# Voltage_Current_Sense.net
KiCad netlist of a schematic drawn in Altium Designer
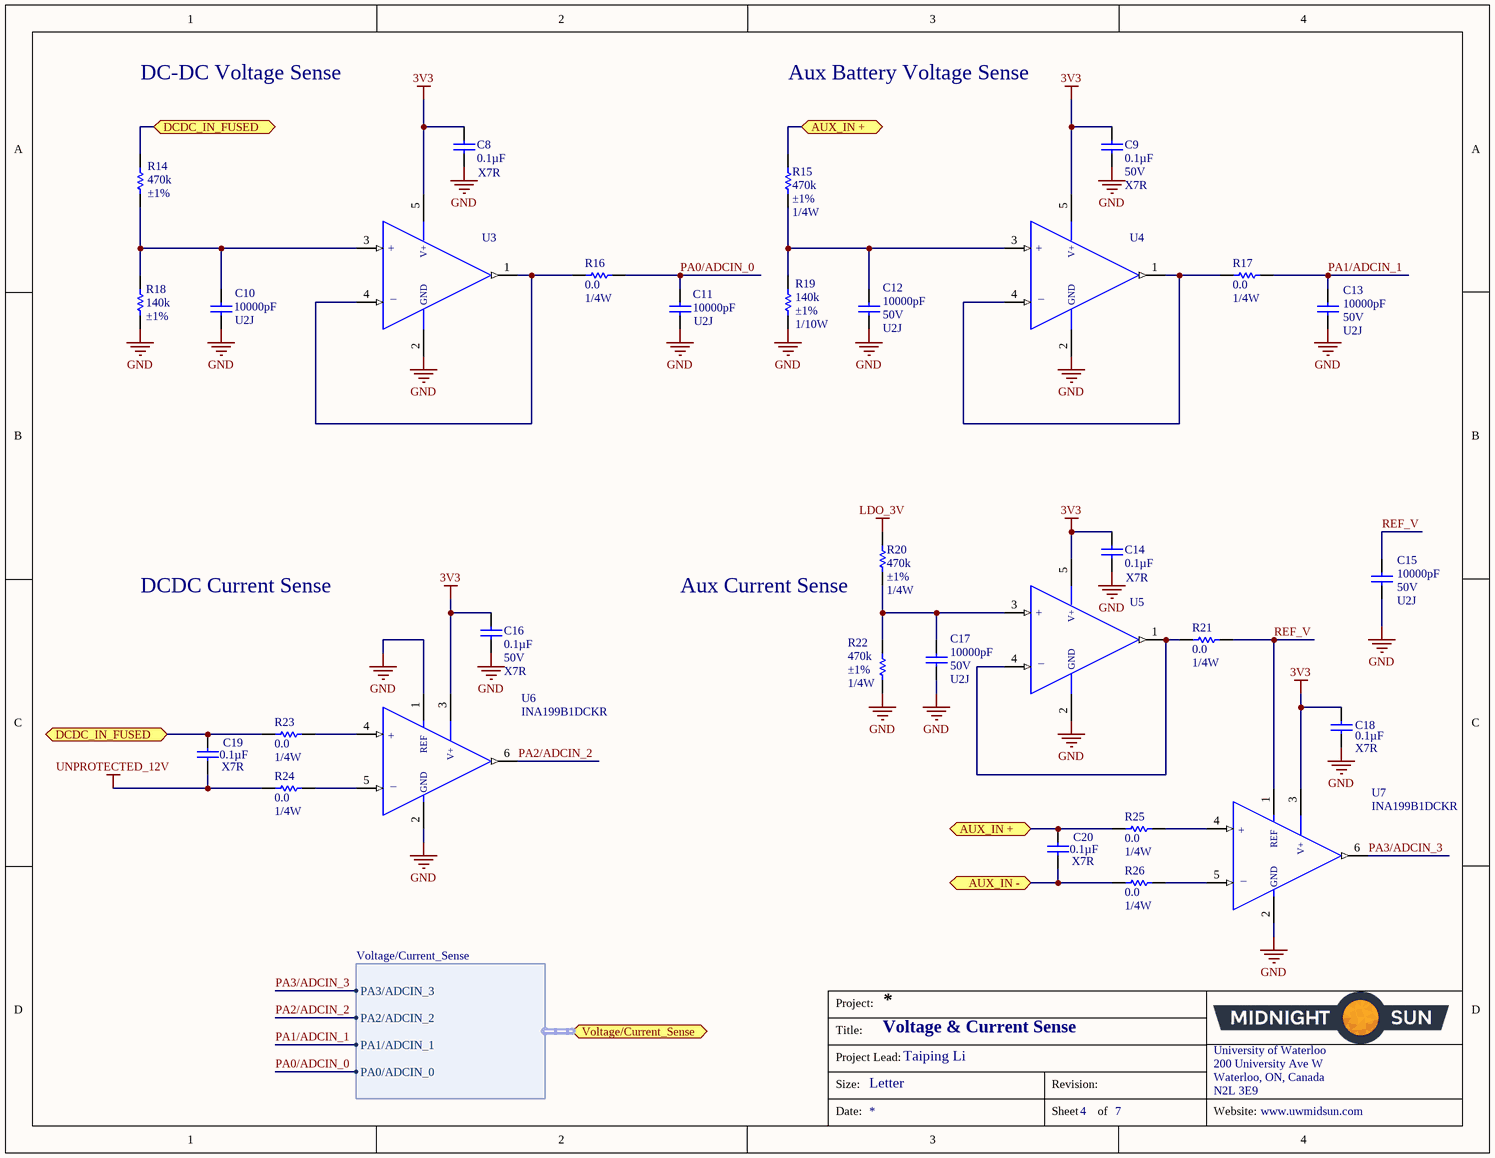
[diagram p0: Voltage&Current_Sense.SchDoc]

(export (version "E")
  (design (tool "Eeschema 10.0.6"))
  (components
    (comp (ref "C8")
      (value "CAP CER 0.1UF 50V 10% X7R 0603")
      (footprint "CAP, 0603")
      (description "0.10µF ±10% 50V Ceramic Capacitor X7R 0603 (1608 Metric)")
      (fields
        (field (name "TOLERANCE") "±10%")
        (field (name "CAPACITANCE") "0.1µF")
        (field (name "TEMPERATURE COEFFICIENT") "X7R")
      )
      (libsource (lib "Schematic Diagrams") (part "CAP CER 0.1UF 50V 10% X7R 0603"))
    )
    (comp (ref "C9")
      (value "CAP CER 0.1UF 50V 10% X7R 0603")
      (footprint "CAP, 0603")
      (description "0.10µF ±10% 50V Ceramic Capacitor X7R 0603 (1608 Metric)")
      (fields
        (field (name "TOLERANCE") "±10%")
        (field (name "CAPACITANCE") "0.1µF")
        (field (name "VOLTAGE") "50V")
        (field (name "TEMPERATURE COEFFICIENT") "X7R")
      )
      (libsource (lib "Schematic Diagrams") (part "CAP CER 0.1UF 50V 10% X7R 0603"))
    )
    (comp (ref "C10")
      (value "CAP CER 10nF 50V 5% X7R 0603")
      (footprint "CAP, 0603")
      (description "10000pF ±5% 50V Ceramic Capacitor U2J 0603 (1608 Metric)")
      (fields
        (field (name "TOLERANCE") "±5%")
        (field (name "CAPACITANCE") "10000pF")
        (field (name "TEMPERATURE COEFFICIENT") "U2J")
        (field (name "VOLTAGE") "50V")
      )
      (libsource (lib "Schematic Diagrams") (part "CAP CER 10nF 50V 5% X7R 0603"))
    )
    (comp (ref "C11")
      (value "CAP CER 10nF 50V 5% X7R 0603")
      (footprint "CAP, 0603")
      (description "10000pF ±5% 50V Ceramic Capacitor U2J 0603 (1608 Metric)")
      (fields
        (field (name "TOLERANCE") "±5%")
        (field (name "CAPACITANCE") "10000pF")
        (field (name "TEMPERATURE COEFFICIENT") "U2J")
        (field (name "VOLTAGE") "50V")
      )
      (libsource (lib "Schematic Diagrams") (part "CAP CER 10nF 50V 5% X7R 0603"))
    )
    (comp (ref "C12")
      (value "CAP CER 10nF 50V 5% X7R 0603")
      (footprint "CAP, 0603")
      (description "10000pF ±5% 50V Ceramic Capacitor U2J 0603 (1608 Metric)")
      (fields
        (field (name "TOLERANCE") "±5%")
        (field (name "CAPACITANCE") "10000pF")
        (field (name "VOLTAGE") "50V")
        (field (name "TEMPERATURE COEFFICIENT") "U2J")
      )
      (libsource (lib "Schematic Diagrams") (part "CAP CER 10nF 50V 5% X7R 0603"))
    )
    (comp (ref "C13")
      (value "CAP CER 10nF 50V 5% X7R 0603")
      (footprint "CAP, 0603")
      (description "10000pF ±5% 50V Ceramic Capacitor U2J 0603 (1608 Metric)")
      (fields
        (field (name "TOLERANCE") "±5%")
        (field (name "CAPACITANCE") "10000pF")
        (field (name "VOLTAGE") "50V")
        (field (name "TEMPERATURE COEFFICIENT") "U2J")
      )
      (libsource (lib "Schematic Diagrams") (part "CAP CER 10nF 50V 5% X7R 0603"))
    )
    (comp (ref "C14")
      (value "CAP CER 0.1UF 50V 10% X7R 0603")
      (footprint "CAP, 0603")
      (description "0.10µF ±10% 50V Ceramic Capacitor X7R 0603 (1608 Metric)")
      (fields
        (field (name "TOLERANCE") "±10%")
        (field (name "CAPACITANCE") "0.1µF")
        (field (name "TEMPERATURE COEFFICIENT") "X7R")
      )
      (libsource (lib "Schematic Diagrams") (part "CAP CER 0.1UF 50V 10% X7R 0603"))
    )
    (comp (ref "C15")
      (value "CAP CER 10nF 50V 5% X7R 0603")
      (footprint "CAP, 0603")
      (description "10000pF ±5% 50V Ceramic Capacitor U2J 0603 (1608 Metric)")
      (fields
        (field (name "TOLERANCE") "±5%")
        (field (name "CAPACITANCE") "10000pF")
        (field (name "VOLTAGE") "50V")
        (field (name "TEMPERATURE COEFFICIENT") "U2J")
      )
      (libsource (lib "Schematic Diagrams") (part "CAP CER 10nF 50V 5% X7R 0603"))
    )
    (comp (ref "C16")
      (value "CAP CER 0.1UF 50V 10% X7R 0603")
      (footprint "CAP, 0603")
      (description "0.10µF ±10% 50V Ceramic Capacitor X7R 0603 (1608 Metric)")
      (fields
        (field (name "TOLERANCE") "±10%")
        (field (name "CAPACITANCE") "0.1µF")
        (field (name "VOLTAGE") "50V")
        (field (name "TEMPERATURE COEFFICIENT") "X7R")
      )
      (libsource (lib "Schematic Diagrams") (part "CAP CER 0.1UF 50V 10% X7R 0603"))
    )
    (comp (ref "C17")
      (value "CAP CER 10nF 50V 5% X7R 0603")
      (footprint "CAP, 0603")
      (description "10000pF ±5% 50V Ceramic Capacitor U2J 0603 (1608 Metric)")
      (fields
        (field (name "TOLERANCE") "±5%")
        (field (name "CAPACITANCE") "10000pF")
        (field (name "VOLTAGE") "50V")
        (field (name "TEMPERATURE COEFFICIENT") "U2J")
      )
      (libsource (lib "Schematic Diagrams") (part "CAP CER 10nF 50V 5% X7R 0603"))
    )
    (comp (ref "C18")
      (value "CAP CER 0.1UF 50V 10% X7R 0603")
      (footprint "CAP, 0603")
      (description "0.10µF ±10% 50V Ceramic Capacitor X7R 0603 (1608 Metric)")
      (fields
        (field (name "TOLERANCE") "±10%")
        (field (name "CAPACITANCE") "0.1µF")
        (field (name "TEMPERATURE COEFFICIENT") "X7R")
      )
      (libsource (lib "Schematic Diagrams") (part "CAP CER 0.1UF 50V 10% X7R 0603"))
    )
    (comp (ref "C19")
      (value "CAP CER 0.1UF 50V 10% X7R 0603")
      (footprint "CAP, 0603")
      (description "0.10µF ±10% 50V Ceramic Capacitor X7R 0603 (1608 Metric)")
      (fields
        (field (name "TOLERANCE") "±10%")
        (field (name "CAPACITANCE") "0.1µF")
        (field (name "TEMPERATURE COEFFICIENT") "X7R")
      )
      (libsource (lib "Schematic Diagrams") (part "CAP CER 0.1UF 50V 10% X7R 0603"))
    )
    (comp (ref "C20")
      (value "CAP CER 0.1UF 50V 10% X7R 0603")
      (footprint "CAP, 0603")
      (description "0.10µF ±10% 50V Ceramic Capacitor X7R 0603 (1608 Metric)")
      (fields
        (field (name "TOLERANCE") "±10%")
        (field (name "CAPACITANCE") "0.1µF")
        (field (name "TEMPERATURE COEFFICIENT") "X7R")
      )
      (libsource (lib "Schematic Diagrams") (part "CAP CER 0.1UF 50V 10% X7R 0603"))
    )
    (comp (ref "R14")
      (value "RES 470K OHM 1% 1/4W 0603")
      (footprint "RES, 0603")
      (description "RES SMD 470K OHM 1% 1/4W 0603")
      (fields (field (name "RESISTANCE") "470k") (field (name "TOLERANCE") "±1%"))
      (libsource (lib "Schematic Diagrams") (part "RES 470K OHM 1% 1/4W 0603"))
    )
    (comp (ref "R15")
      (value "RES 470K OHM 1% 1/4W 0603")
      (footprint "RES, 0603")
      (description "RES SMD 470K OHM 1% 1/4W 0603")
      (fields
        (field (name "RESISTANCE") "470k")
        (field (name "TOLERANCE") "±1%")
        (field (name "POWER") "1/4W")
      )
      (libsource (lib "Schematic Diagrams") (part "RES 470K OHM 1% 1/4W 0603"))
    )
    (comp (ref "R16")
      (value "RES 0.0 OHM 1/4W 0603")
      (footprint "RES, 0603")
      (description "RES SMD 0.0 OHM JUMPER 1/4W 0603")
      (fields (field (name "RESISTANCE") "0.0") (field (name "POWER (WATTS)") "1/4W"))
      (libsource (lib "Schematic Diagrams") (part "RES 0.0 OHM 1/4W 0603"))
    )
    (comp (ref "R17")
      (value "RES 0.0 OHM 1/4W 0603")
      (footprint "RES, 0603")
      (description "RES SMD 0.0 OHM JUMPER 1/4W 0603")
      (fields (field (name "RESISTANCE") "0.0") (field (name "POWER (WATTS)") "1/4W"))
      (libsource (lib "Schematic Diagrams") (part "RES 0.0 OHM 1/4W 0603"))
    )
    (comp (ref "R18")
      (value "RES 140K OHM 1% 1/10W 0603")
      (footprint "RES, 0603")
      (fields (field (name "RESISTANCE (OHMS)") "140k") (field (name "TOLERANCE") "±1%"))
      (libsource (lib "Schematic Diagrams") (part "RES 140K OHM 1% 1/10W 0603"))
    )
    (comp (ref "R19")
      (value "RES 140K OHM 1% 1/10W 0603")
      (footprint "RES, 0603")
      (fields
        (field (name "RESISTANCE (OHMS)") "140k")
        (field (name "TOLERANCE") "±1%")
        (field (name "POWER (WATTS)") "1/10W")
      )
      (libsource (lib "Schematic Diagrams") (part "RES 140K OHM 1% 1/10W 0603"))
    )
    (comp (ref "R20")
      (value "RES 470K OHM 1% 1/4W 0603")
      (footprint "RES, 0603")
      (description "RES SMD 470K OHM 1% 1/4W 0603")
      (fields
        (field (name "RESISTANCE") "470k")
        (field (name "TOLERANCE") "±1%")
        (field (name "POWER") "1/4W")
      )
      (libsource (lib "Schematic Diagrams") (part "RES 470K OHM 1% 1/4W 0603"))
    )
    (comp (ref "R21")
      (value "RES 0.0 OHM 1/4W 0603")
      (footprint "RES, 0603")
      (description "RES SMD 0.0 OHM JUMPER 1/4W 0603")
      (fields (field (name "RESISTANCE") "0.0") (field (name "POWER (WATTS)") "1/4W"))
      (libsource (lib "Schematic Diagrams") (part "RES 0.0 OHM 1/4W 0603"))
    )
    (comp (ref "R22")
      (value "RES 470K OHM 1% 1/4W 0603")
      (footprint "RES, 0603")
      (description "RES SMD 470K OHM 1% 1/4W 0603")
      (fields
        (field (name "RESISTANCE") "470k")
        (field (name "TOLERANCE") "±1%")
        (field (name "POWER") "1/4W")
      )
      (libsource (lib "Schematic Diagrams") (part "RES 470K OHM 1% 1/4W 0603"))
    )
    (comp (ref "R23")
      (value "RES 0.0 OHM 1/4W 0603")
      (footprint "RES, 0603")
      (description "RES SMD 0.0 OHM JUMPER 1/4W 0603")
      (fields (field (name "RESISTANCE") "0.0") (field (name "POWER (WATTS)") "1/4W"))
      (libsource (lib "Schematic Diagrams") (part "RES 0.0 OHM 1/4W 0603"))
    )
    (comp (ref "R24")
      (value "RES 0.0 OHM 1/4W 0603")
      (footprint "RES, 0603")
      (description "RES SMD 0.0 OHM JUMPER 1/4W 0603")
      (fields (field (name "RESISTANCE") "0.0") (field (name "POWER (WATTS)") "1/4W"))
      (libsource (lib "Schematic Diagrams") (part "RES 0.0 OHM 1/4W 0603"))
    )
    (comp (ref "R25")
      (value "RES 0.0 OHM 1/4W 0603")
      (footprint "RES, 0603")
      (description "RES SMD 0.0 OHM JUMPER 1/4W 0603")
      (fields (field (name "RESISTANCE") "0.0") (field (name "POWER (WATTS)") "1/4W"))
      (libsource (lib "Schematic Diagrams") (part "RES 0.0 OHM 1/4W 0603"))
    )
    (comp (ref "R26")
      (value "RES 0.0 OHM 1/4W 0603")
      (footprint "RES, 0603")
      (description "RES SMD 0.0 OHM JUMPER 1/4W 0603")
      (fields (field (name "RESISTANCE") "0.0") (field (name "POWER (WATTS)") "1/4W"))
      (libsource (lib "Schematic Diagrams") (part "RES 0.0 OHM 1/4W 0603"))
    )
    (comp (ref "U3")
      (value "IC OP AMP GEN PURPOSE RR 10MHZ SOT-23-5")
      (footprint "IC OP AMP GP RR 10MHZ SOT-23-5")
      (description "General Purpose Amplifier 1 Circuit Rail-to-Rail SOT-23-5")
      (libsource (lib "Schematic Diagrams") (part "IC OP AMP GEN PURPOSE RR 10MHZ SOT-23-5"))
    )
    (comp (ref "U4")
      (value "IC OP AMP GEN PURPOSE RR 10MHZ SOT-23-5")
      (footprint "IC OP AMP GP RR 10MHZ SOT-23-5")
      (description "General Purpose Amplifier 1 Circuit Rail-to-Rail SOT-23-5")
      (libsource (lib "Schematic Diagrams") (part "IC OP AMP GEN PURPOSE RR 10MHZ SOT-23-5"))
    )
    (comp (ref "U5")
      (value "IC OP AMP GEN PURPOSE RR 10MHZ SOT-23-5")
      (footprint "IC OP AMP GP RR 10MHZ SOT-23-5")
      (description "General Purpose Amplifier 1 Circuit Rail-to-Rail SOT-23-5")
      (libsource (lib "Schematic Diagrams") (part "IC OP AMP GEN PURPOSE RR 10MHZ SOT-23-5"))
    )
    (comp (ref "U6")
      (value "IC CURRENT AMPLIFIER SC70-6")
      (footprint "IC OP AMP CURR SENSE 80KHZ SC70-6")
      (description "Current Sense Amplifier 1 Circuit SC-70-6")
      (fields (field (name "MANUFACTURER PART NUMBER 1") "INA199B1DCKR"))
      (libsource (lib "Schematic Diagrams") (part "IC CURRENT AMPLIFIER SC70-6"))
    )
    (comp (ref "U7")
      (value "IC CURRENT AMPLIFIER SC70-6")
      (footprint "IC OP AMP CURR SENSE 80KHZ SC70-6")
      (description "Current Sense Amplifier 1 Circuit SC-70-6")
      (fields (field (name "MANUFACTURER PART NUMBER 1") "INA199B1DCKR"))
      (libsource (lib "Schematic Diagrams") (part "IC CURRENT AMPLIFIER SC70-6"))
    )
  )
  (nets
    (net (code "2") (name "/AUX_IN +") (class "Default")
      (node (ref "C20") (pin "1") (pinfunction "1_1") (pintype "passive"))
      (node (ref "R15") (pin "1") (pinfunction "1_1") (pintype "passive"))
      (node (ref "R25") (pin "1") (pinfunction "1_1") (pintype "passive"))
    )
    (net (code "3") (name "/AUX_IN -") (class "Default")
      (node (ref "C20") (pin "2") (pinfunction "2_2") (pintype "passive"))
      (node (ref "R26") (pin "1") (pinfunction "1_1") (pintype "passive"))
    )
    (net (code "4") (name "/DCDC_IN_FUSED") (class "Default")
      (node (ref "C19") (pin "1") (pinfunction "1_1") (pintype "passive"))
      (node (ref "R14") (pin "1") (pinfunction "1_1") (pintype "passive"))
      (node (ref "R23") (pin "1") (pinfunction "1_1") (pintype "passive"))
    )
    (net (code "5") (name "/PA0{slash}ADCIN_0") (class "Default")
      (node (ref "C11") (pin "1") (pinfunction "1_1") (pintype "passive"))
      (node (ref "R16") (pin "2") (pinfunction "2_2") (pintype "passive"))
    )
    (net (code "6") (name "/PA1{slash}ADCIN_1") (class "Default")
      (node (ref "C13") (pin "1") (pinfunction "1_1") (pintype "passive"))
      (node (ref "R17") (pin "2") (pinfunction "2_2") (pintype "passive"))
    )
    (net (code "7") (name "/PA2{slash}ADCIN_2") (class "Default")
      (node (ref "U6") (pin "6") (pinfunction "OUTPUT_6") (pintype "output"))
    )
    (net (code "8") (name "/PA3{slash}ADCIN_3") (class "Default")
      (node (ref "U7") (pin "6") (pinfunction "OUTPUT_6") (pintype "output"))
    )
    (net (code "9") (name "/REF_V") (class "Default")
      (node (ref "C15") (pin "1") (pinfunction "1_1") (pintype "passive"))
      (node (ref "R21") (pin "2") (pinfunction "2_2") (pintype "passive"))
      (node (ref "U7") (pin "1") (pinfunction "REF_1") (pintype "passive"))
    )
    (net (code "11") (name "3V3") (class "Default")
      (node (ref "C14") (pin "1") (pinfunction "1_1") (pintype "passive"))
      (node (ref "C16") (pin "1") (pinfunction "1_1") (pintype "passive"))
      (node (ref "C18") (pin "1") (pinfunction "1_1") (pintype "passive"))
      (node (ref "C8") (pin "1") (pinfunction "1_1") (pintype "passive"))
      (node (ref "C9") (pin "1") (pinfunction "1_1") (pintype "passive"))
      (node (ref "U3") (pin "5") (pinfunction "VDD_5") (pintype "power_in"))
      (node (ref "U4") (pin "5") (pinfunction "VDD_5") (pintype "power_in"))
      (node (ref "U5") (pin "5") (pinfunction "VDD_5") (pintype "power_in"))
      (node (ref "U6") (pin "3") (pinfunction "V+_3") (pintype "power_in"))
      (node (ref "U7") (pin "3") (pinfunction "V+_3") (pintype "power_in"))
    )
    (net (code "12") (name "GND") (class "Default")
      (node (ref "C10") (pin "2") (pinfunction "2_2") (pintype "passive"))
      (node (ref "C11") (pin "2") (pinfunction "2_2") (pintype "passive"))
      (node (ref "C12") (pin "2") (pinfunction "2_2") (pintype "passive"))
      (node (ref "C13") (pin "2") (pinfunction "2_2") (pintype "passive"))
      (node (ref "C14") (pin "2") (pinfunction "2_2") (pintype "passive"))
      (node (ref "C15") (pin "2") (pinfunction "2_2") (pintype "passive"))
      (node (ref "C16") (pin "2") (pinfunction "2_2") (pintype "passive"))
      (node (ref "C17") (pin "2") (pinfunction "2_2") (pintype "passive"))
      (node (ref "C18") (pin "2") (pinfunction "2_2") (pintype "passive"))
      (node (ref "C8") (pin "2") (pinfunction "2_2") (pintype "passive"))
      (node (ref "C9") (pin "2") (pinfunction "2_2") (pintype "passive"))
      (node (ref "R18") (pin "2") (pinfunction "2_2") (pintype "passive"))
      (node (ref "R19") (pin "2") (pinfunction "2_2") (pintype "passive"))
      (node (ref "R22") (pin "2") (pinfunction "2_2") (pintype "passive"))
      (node (ref "U3") (pin "2") (pinfunction "VSS_2") (pintype "power_in"))
      (node (ref "U4") (pin "2") (pinfunction "VSS_2") (pintype "power_in"))
      (node (ref "U5") (pin "2") (pinfunction "VSS_2") (pintype "power_in"))
      (node (ref "U6") (pin "1") (pinfunction "REF_1") (pintype "passive"))
      (node (ref "U6") (pin "2") (pinfunction "GND_2") (pintype "power_in"))
      (node (ref "U7") (pin "2") (pinfunction "GND_2") (pintype "power_in"))
    )
    (net (code "13") (name "LDO_3V") (class "Default")
      (node (ref "R20") (pin "1") (pinfunction "1_1") (pintype "passive"))
    )
    (net (code "14") (name "Net-(U3-+IN)") (class "Default")
      (node (ref "C10") (pin "1") (pinfunction "1_1") (pintype "passive"))
      (node (ref "R14") (pin "2") (pinfunction "2_2") (pintype "passive"))
      (node (ref "R18") (pin "1") (pinfunction "1_1") (pintype "passive"))
      (node (ref "U3") (pin "3") (pinfunction "+IN_3") (pintype "input"))
    )
    (net (code "15") (name "Net-(U3--IN)") (class "Default")
      (node (ref "R16") (pin "1") (pinfunction "1_1") (pintype "passive"))
      (node (ref "U3") (pin "1") (pinfunction "OUTPUT_1") (pintype "output"))
      (node (ref "U3") (pin "4") (pinfunction "-IN_4") (pintype "input"))
    )
    (net (code "16") (name "Net-(U4-+IN)") (class "Default")
      (node (ref "C12") (pin "1") (pinfunction "1_1") (pintype "passive"))
      (node (ref "R15") (pin "2") (pinfunction "2_2") (pintype "passive"))
      (node (ref "R19") (pin "1") (pinfunction "1_1") (pintype "passive"))
      (node (ref "U4") (pin "3") (pinfunction "+IN_3") (pintype "input"))
    )
    (net (code "17") (name "Net-(U4--IN)") (class "Default")
      (node (ref "R17") (pin "1") (pinfunction "1_1") (pintype "passive"))
      (node (ref "U4") (pin "1") (pinfunction "OUTPUT_1") (pintype "output"))
      (node (ref "U4") (pin "4") (pinfunction "-IN_4") (pintype "input"))
    )
    (net (code "18") (name "Net-(U5-+IN)") (class "Default")
      (node (ref "C17") (pin "1") (pinfunction "1_1") (pintype "passive"))
      (node (ref "R20") (pin "2") (pinfunction "2_2") (pintype "passive"))
      (node (ref "R22") (pin "1") (pinfunction "1_1") (pintype "passive"))
      (node (ref "U5") (pin "3") (pinfunction "+IN_3") (pintype "input"))
    )
    (net (code "19") (name "Net-(U5--IN)") (class "Default")
      (node (ref "R21") (pin "1") (pinfunction "1_1") (pintype "passive"))
      (node (ref "U5") (pin "1") (pinfunction "OUTPUT_1") (pintype "output"))
      (node (ref "U5") (pin "4") (pinfunction "-IN_4") (pintype "input"))
    )
    (net (code "20") (name "Net-(U6-+IN)") (class "Default")
      (node (ref "R23") (pin "2") (pinfunction "2_2") (pintype "passive"))
      (node (ref "U6") (pin "4") (pinfunction "+IN_4") (pintype "input"))
    )
    (net (code "21") (name "Net-(U6--IN)") (class "Default")
      (node (ref "R24") (pin "2") (pinfunction "2_2") (pintype "passive"))
      (node (ref "U6") (pin "5") (pinfunction "-IN_5") (pintype "input"))
    )
    (net (code "22") (name "Net-(U7-+IN)") (class "Default")
      (node (ref "R25") (pin "2") (pinfunction "2_2") (pintype "passive"))
      (node (ref "U7") (pin "4") (pinfunction "+IN_4") (pintype "input"))
    )
    (net (code "23") (name "Net-(U7--IN)") (class "Default")
      (node (ref "R26") (pin "2") (pinfunction "2_2") (pintype "passive"))
      (node (ref "U7") (pin "5") (pinfunction "-IN_5") (pintype "input"))
    )
    (net (code "24") (name "UNPROTECTED_12V") (class "Default")
      (node (ref "C19") (pin "2") (pinfunction "2_2") (pintype "passive"))
      (node (ref "R24") (pin "1") (pinfunction "1_1") (pintype "passive"))
    )
  )
)
